# Power.net
KiCad netlist of a schematic drawn in Altium Designer
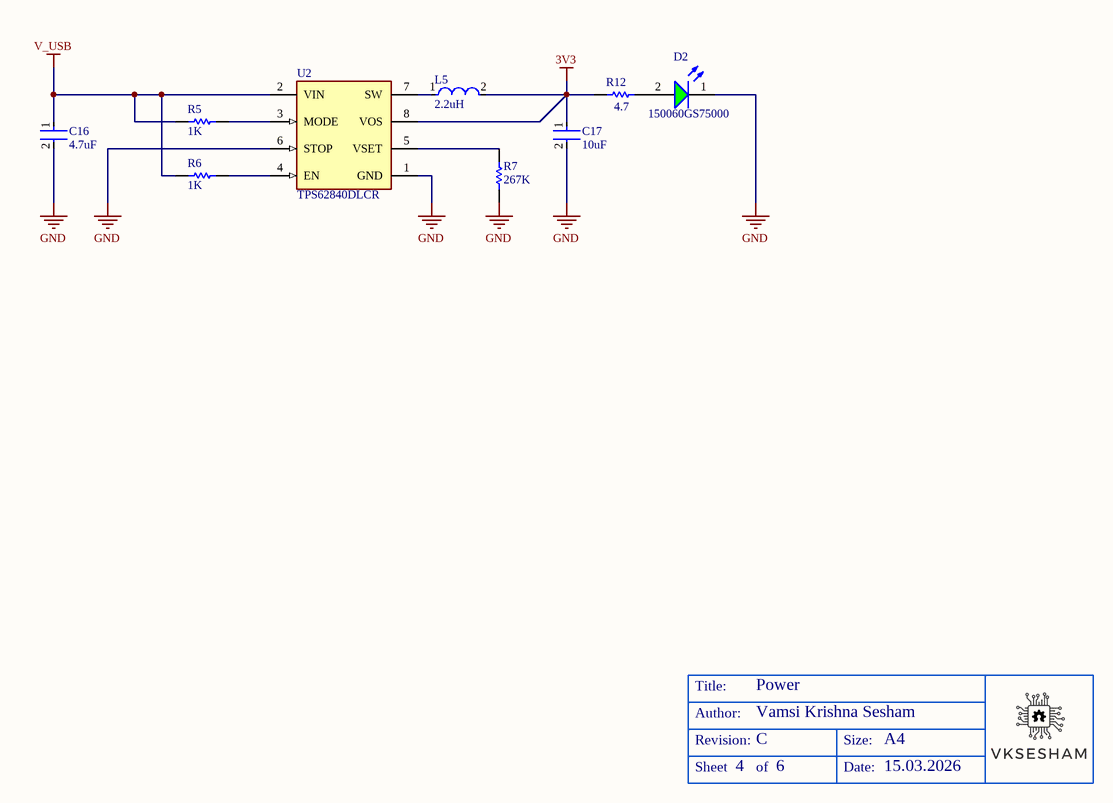
[diagram p0: Power.SchDoc]

(export (version "E")
  (design (tool "Eeschema 10.0.6"))
  (components
    (comp (ref "C16")
      (value "4.7uF")
      (footprint "FP-CC0402-MFG")
      (description "CAP CER 4.7UF 16V X5R 0402")
      (fields
        (field (name "OCTOPART") "https://octopart.com/cc0402mrx5r7bb475-yageo-81932628")
        (field (name "MANUFACTURER PART NUMBER") "CC0402MRX5R7BB475")
      )
      (libsource (lib "Altium Content Vault") (part "11868f565c42a9108669ba33697ecf6"))
    )
    (comp (ref "C17")
      (value "10uF")
      (footprint "FP-CL07-IPC_C")
      (description "Cap Ceramic 10uF 10V X5R ±20% SMD 0402 +85°C Paper T/R")
      (fields (field (name "TOLERANCE") "20%"))
      (libsource (lib "Altium Content Vault") (part "b4654b650e69147ec39a6b967a45e02"))
    )
    (comp (ref "D2")
      (value "150060GS75000")
      (footprint "WL-SMCW_0603_150060xx75000")
      (description "430mcd Colorless transparence 520nm Emerald 140° LED0603 Light Emitting Diodes (LED) ROHS")
      (libsource (lib "Altium Content Vault") (part "LED_Green_2A-1K"))
    )
    (comp (ref "L5")
      (value "2.2uH")
      (footprint "FP-DFE201612C-MFG")
      (description "Shielded Wirewound Inductor 2.2uH 20% 1800mA 0.116Ω 0806 (2016)")
      (libsource (lib "Altium Content Vault") (part "725321dda6339637d4d059423bc1c3c"))
    )
    (comp (ref "R5")
      (value "1K")
      (footprint "RESC0603X28X15ML05T05")
      (fields (field (name "MANUFACTURER") "Vishay Dale") (field (name "PART NUMBER") "CRCW02011K00FNED"))
      (libsource (lib "Altium Content Vault") (part "RES"))
    )
    (comp (ref "R6")
      (value "1K")
      (footprint "RESC0603X28X15ML05T05")
      (fields (field (name "MANUFACTURER") "Vishay Dale") (field (name "PART NUMBER") "CRCW02011K00FNED"))
      (libsource (lib "Altium Content Vault") (part "RES"))
    )
    (comp (ref "R7")
      (value "267K")
      (footprint "RESC1005X40X25ML05T05")
      (fields (field (name "PART NUMBER") "ERJ-2RKF2673X") (field (name "MANUFACTURER") "Panasonic"))
      (libsource (lib "Altium Content Vault") (part "RES"))
    )
    (comp (ref "R12")
      (value "4.7")
      (footprint "RESC0402(1005)_M")
      (description "4R7 0.063W 5% 0402 (1005 Metric)  SMD")
      (fields (field (name "POWER") "0.063 W") (field (name "TOLERANCE") "5 %"))
      (libsource (lib "Altium Content Vault") (part "RES"))
    )
    (comp (ref "U2")
      (value "TPS62840DLCR")
      (footprint "FP-DLC0008B-MFG")
      (description "ULTRA LOW IQ BUCK CONVERTER")
      (fields
        (field (name "OCTOPART") "https://octopart.com/tps62840dlcr-texas+instruments-103121111")
        (field (name "MANUFACTURER") "Texas Instruments")
      )
      (libsource (lib "Altium Content Vault") (part "09bc3a9b1d58a1376198d6b923e8c7c"))
    )
  )
  (nets
    (net (code "1") (name "3V3") (class "Default")
      (node (ref "C17") (pin "1") (pinfunction "1_1") (pintype "passive"))
      (node (ref "L5") (pin "2") (pinfunction "2_2") (pintype "passive"))
      (node (ref "R12") (pin "1") (pinfunction "1_1") (pintype "passive"))
      (node (ref "U2") (pin "8") (pinfunction "VOS_8") (pintype "passive"))
    )
    (net (code "2") (name "GND") (class "Default")
      (node (ref "C16") (pin "2") (pinfunction "2_2") (pintype "passive"))
      (node (ref "C17") (pin "2") (pinfunction "2_2") (pintype "passive"))
      (node (ref "D2") (pin "1") (pinfunction "K_1") (pintype "passive"))
      (node (ref "R7") (pin "1") (pinfunction "1_1") (pintype "passive"))
      (node (ref "U2") (pin "1") (pinfunction "GND_1") (pintype "power_in"))
      (node (ref "U2") (pin "6") (pinfunction "STOP_6") (pintype "input"))
    )
    (net (code "3") (name "Net-(D2-A)") (class "Default")
      (node (ref "D2") (pin "2") (pinfunction "A_2") (pintype "passive"))
      (node (ref "R12") (pin "2") (pinfunction "2_2") (pintype "passive"))
    )
    (net (code "4") (name "Net-(U2-EN)") (class "Default")
      (node (ref "R6") (pin "2") (pinfunction "2_2") (pintype "passive"))
      (node (ref "U2") (pin "4") (pinfunction "EN_4") (pintype "input"))
    )
    (net (code "5") (name "Net-(U2-MODE)") (class "Default")
      (node (ref "R5") (pin "2") (pinfunction "2_2") (pintype "passive"))
      (node (ref "U2") (pin "3") (pinfunction "MODE_3") (pintype "input"))
    )
    (net (code "6") (name "Net-(U2-SW)") (class "Default")
      (node (ref "L5") (pin "1") (pinfunction "1_1") (pintype "passive"))
      (node (ref "U2") (pin "7") (pinfunction "SW_7") (pintype "passive"))
    )
    (net (code "7") (name "Net-(U2-VSET)") (class "Default")
      (node (ref "R7") (pin "2") (pinfunction "2_2") (pintype "passive"))
      (node (ref "U2") (pin "5") (pinfunction "VSET_5") (pintype "passive"))
    )
    (net (code "8") (name "V_USB") (class "Default")
      (node (ref "C16") (pin "1") (pinfunction "1_1") (pintype "passive"))
      (node (ref "R5") (pin "1") (pinfunction "1_1") (pintype "passive"))
      (node (ref "R6") (pin "1") (pinfunction "1_1") (pintype "passive"))
      (node (ref "U2") (pin "2") (pinfunction "VIN_2") (pintype "power_in"))
    )
  )
)
